# ASBB_FireflyX1.net
KiCad netlist of a schematic drawn in Altium Designer
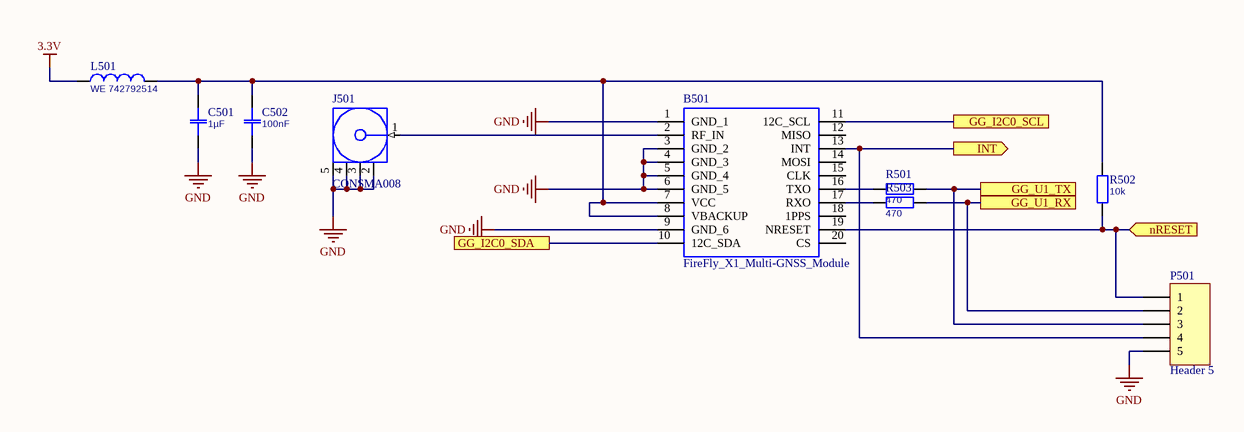
[diagram p0: ASBB_FireflyX1.SchDoc]

(export (version "E")
  (design (tool "Eeschema 10.0.6"))
  (components
    (comp (ref "B501")
      (value "FireFly_X1_Multi-GNSS_Module")
      (footprint "X-1:X-1")
      (description "Dual system GNSS receiver Module, QFN-20")
      (fields (field (name "MANUFACTURER_PART_NUMBER") "FireFly X1 Multi-GNSS Module"))
      (libsource (lib "FireFly_X1_Multi-GNSS_Module") (part "FireFly_X1_Multi-GNSS_Module"))
    )
    (comp (ref "C501")
      (value "1µF")
      (footprint "0603")
      (description "Capacitor")
      (fields (field (name "PARTNUMBER") "?"))
      (libsource (lib "FZI") (part "Capacitor"))
    )
    (comp (ref "C502")
      (value "100nF")
      (footprint "0603")
      (description "Capacitor")
      (fields (field (name "PARTNUMBER") "?"))
      (libsource (lib "FZI") (part "Capacitor"))
    )
    (comp (ref "J501")
      (value "CONSMA008")
      (footprint "CON-SMA-L")
      (description "SMA Female PCB Mount Connector - Extended")
      (libsource (lib "Linx Technologies Connector") (part "CONSMA008"))
    )
    (comp (ref "L501")
      (value "WE 742792514")
      (footprint "1812")
      (description "Inductor")
      (fields (field (name "PARTNUMBER") "?"))
      (libsource (lib "FZI") (part "Inductor"))
    )
    (comp (ref "P501")
      (value "Header 5")
      (footprint "HDR1X5")
      (description "Header, 5-Pin")
      (fields (field (name "PUBLISHER") "Altium Limited"))
      (libsource (lib "Miscellaneous Connectors") (part "Header 5"))
    )
    (comp (ref "R501")
      (value "470")
      (footprint "0603")
      (description "Resistor")
      (fields (field (name "PARTNUMBER") "?"))
      (libsource (lib "FZI") (part "Resistor"))
    )
    (comp (ref "R502")
      (value "10k")
      (footprint "0603")
      (description "Resistor")
      (fields (field (name "PARTNUMBER") "?"))
      (libsource (lib "FZI") (part "Resistor"))
    )
    (comp (ref "R503")
      (value "470")
      (footprint "0603")
      (description "Resistor")
      (fields (field (name "PARTNUMBER") "?"))
      (libsource (lib "FZI") (part "Resistor"))
    )
  )
  (nets
    (net (code "1") (name "/GG_I2C0_SCL") (class "Default")
      (node (ref "B501") (pin "11") (pinfunction "12C_SCL_11") (pintype "passive"))
    )
    (net (code "2") (name "/GG_I2C0_SDA") (class "Default")
      (node (ref "B501") (pin "10") (pinfunction "12C_SDA_10") (pintype "passive"))
    )
    (net (code "3") (name "/GG_U1_RX") (class "Default")
      (node (ref "P501") (pin "2") (pinfunction "2_2") (pintype "passive"))
      (node (ref "R503") (pin "2") (pinfunction "2_2") (pintype "passive"))
    )
    (net (code "4") (name "/GG_U1_TX") (class "Default")
      (node (ref "P501") (pin "3") (pinfunction "3_3") (pintype "passive"))
      (node (ref "R501") (pin "2") (pinfunction "2_2") (pintype "passive"))
    )
    (net (code "5") (name "/INT") (class "Default")
      (node (ref "B501") (pin "13") (pinfunction "INT_13") (pintype "passive"))
      (node (ref "P501") (pin "4") (pinfunction "4_4") (pintype "passive"))
    )
    (net (code "6") (name "/nRESET") (class "Default")
      (node (ref "B501") (pin "19") (pinfunction "NRESET_19") (pintype "passive"))
      (node (ref "P501") (pin "1") (pinfunction "1_1") (pintype "passive"))
      (node (ref "R502") (pin "1") (pinfunction "1_1") (pintype "passive"))
    )
    (net (code "7") (name "3.3V") (class "Default")
      (node (ref "L501") (pin "1") (pinfunction "1_1") (pintype "passive"))
    )
    (net (code "8") (name "GND") (class "Default")
      (node (ref "B501") (pin "1") (pinfunction "GND_1_1") (pintype "passive"))
      (node (ref "B501") (pin "3") (pinfunction "GND_2_3") (pintype "passive"))
      (node (ref "B501") (pin "4") (pinfunction "GND_3_4") (pintype "passive"))
      (node (ref "B501") (pin "5") (pinfunction "GND_4_5") (pintype "passive"))
      (node (ref "B501") (pin "6") (pinfunction "GND_5_6") (pintype "passive"))
      (node (ref "B501") (pin "9") (pinfunction "GND_6_9") (pintype "passive"))
      (node (ref "C501") (pin "1") (pinfunction "1_1") (pintype "passive"))
      (node (ref "C502") (pin "1") (pinfunction "1_1") (pintype "passive"))
      (node (ref "J501") (pin "2") (pinfunction "GND_2") (pintype "power_in"))
      (node (ref "J501") (pin "3") (pinfunction "GND_3") (pintype "power_in"))
      (node (ref "J501") (pin "4") (pinfunction "GND_4") (pintype "power_in"))
      (node (ref "J501") (pin "5") (pinfunction "GND_5") (pintype "power_in"))
      (node (ref "P501") (pin "5") (pinfunction "5_5") (pintype "passive"))
    )
    (net (code "9") (name "Net-(B501-RF_IN)") (class "Default")
      (node (ref "B501") (pin "2") (pinfunction "RF_IN_2") (pintype "passive"))
      (node (ref "J501") (pin "1") (pinfunction "Signal_1") (pintype "input"))
    )
    (net (code "10") (name "Net-(B501-RXO)") (class "Default")
      (node (ref "B501") (pin "17") (pinfunction "RXO_17") (pintype "passive"))
      (node (ref "R503") (pin "1") (pinfunction "1_1") (pintype "passive"))
    )
    (net (code "11") (name "Net-(B501-TXO)") (class "Default")
      (node (ref "B501") (pin "16") (pinfunction "TXO_16") (pintype "passive"))
      (node (ref "R501") (pin "1") (pinfunction "1_1") (pintype "passive"))
    )
    (net (code "12") (name "Net-(B501-VBACKUP)") (class "Default")
      (node (ref "B501") (pin "7") (pinfunction "VCC_7") (pintype "passive"))
      (node (ref "B501") (pin "8") (pinfunction "VBACKUP_8") (pintype "passive"))
      (node (ref "C501") (pin "2") (pinfunction "2_2") (pintype "passive"))
      (node (ref "C502") (pin "2") (pinfunction "2_2") (pintype "passive"))
      (node (ref "L501") (pin "2") (pinfunction "2_2") (pintype "passive"))
      (node (ref "R502") (pin "2") (pinfunction "2_2") (pintype "passive"))
    )
    (net (code "13") (name "unconnected-(B501-1PPS-Pad18)") (class "Default")
      (node (ref "B501") (pin "18") (pinfunction "1PPS_18") (pintype "passive"))
    )
    (net (code "14") (name "unconnected-(B501-CLK-Pad15)") (class "Default")
      (node (ref "B501") (pin "15") (pinfunction "CLK_15") (pintype "passive"))
    )
    (net (code "15") (name "unconnected-(B501-CS-Pad20)") (class "Default")
      (node (ref "B501") (pin "20") (pinfunction "CS_20") (pintype "passive"))
    )
    (net (code "16") (name "unconnected-(B501-MISO-Pad12)") (class "Default")
      (node (ref "B501") (pin "12") (pinfunction "MISO_12") (pintype "passive"))
    )
    (net (code "17") (name "unconnected-(B501-MOSI-Pad14)") (class "Default")
      (node (ref "B501") (pin "14") (pinfunction "MOSI_14") (pintype "passive"))
    )
  )
)
